# usb_hub.net
KiCad netlist of a schematic drawn in EAGLE
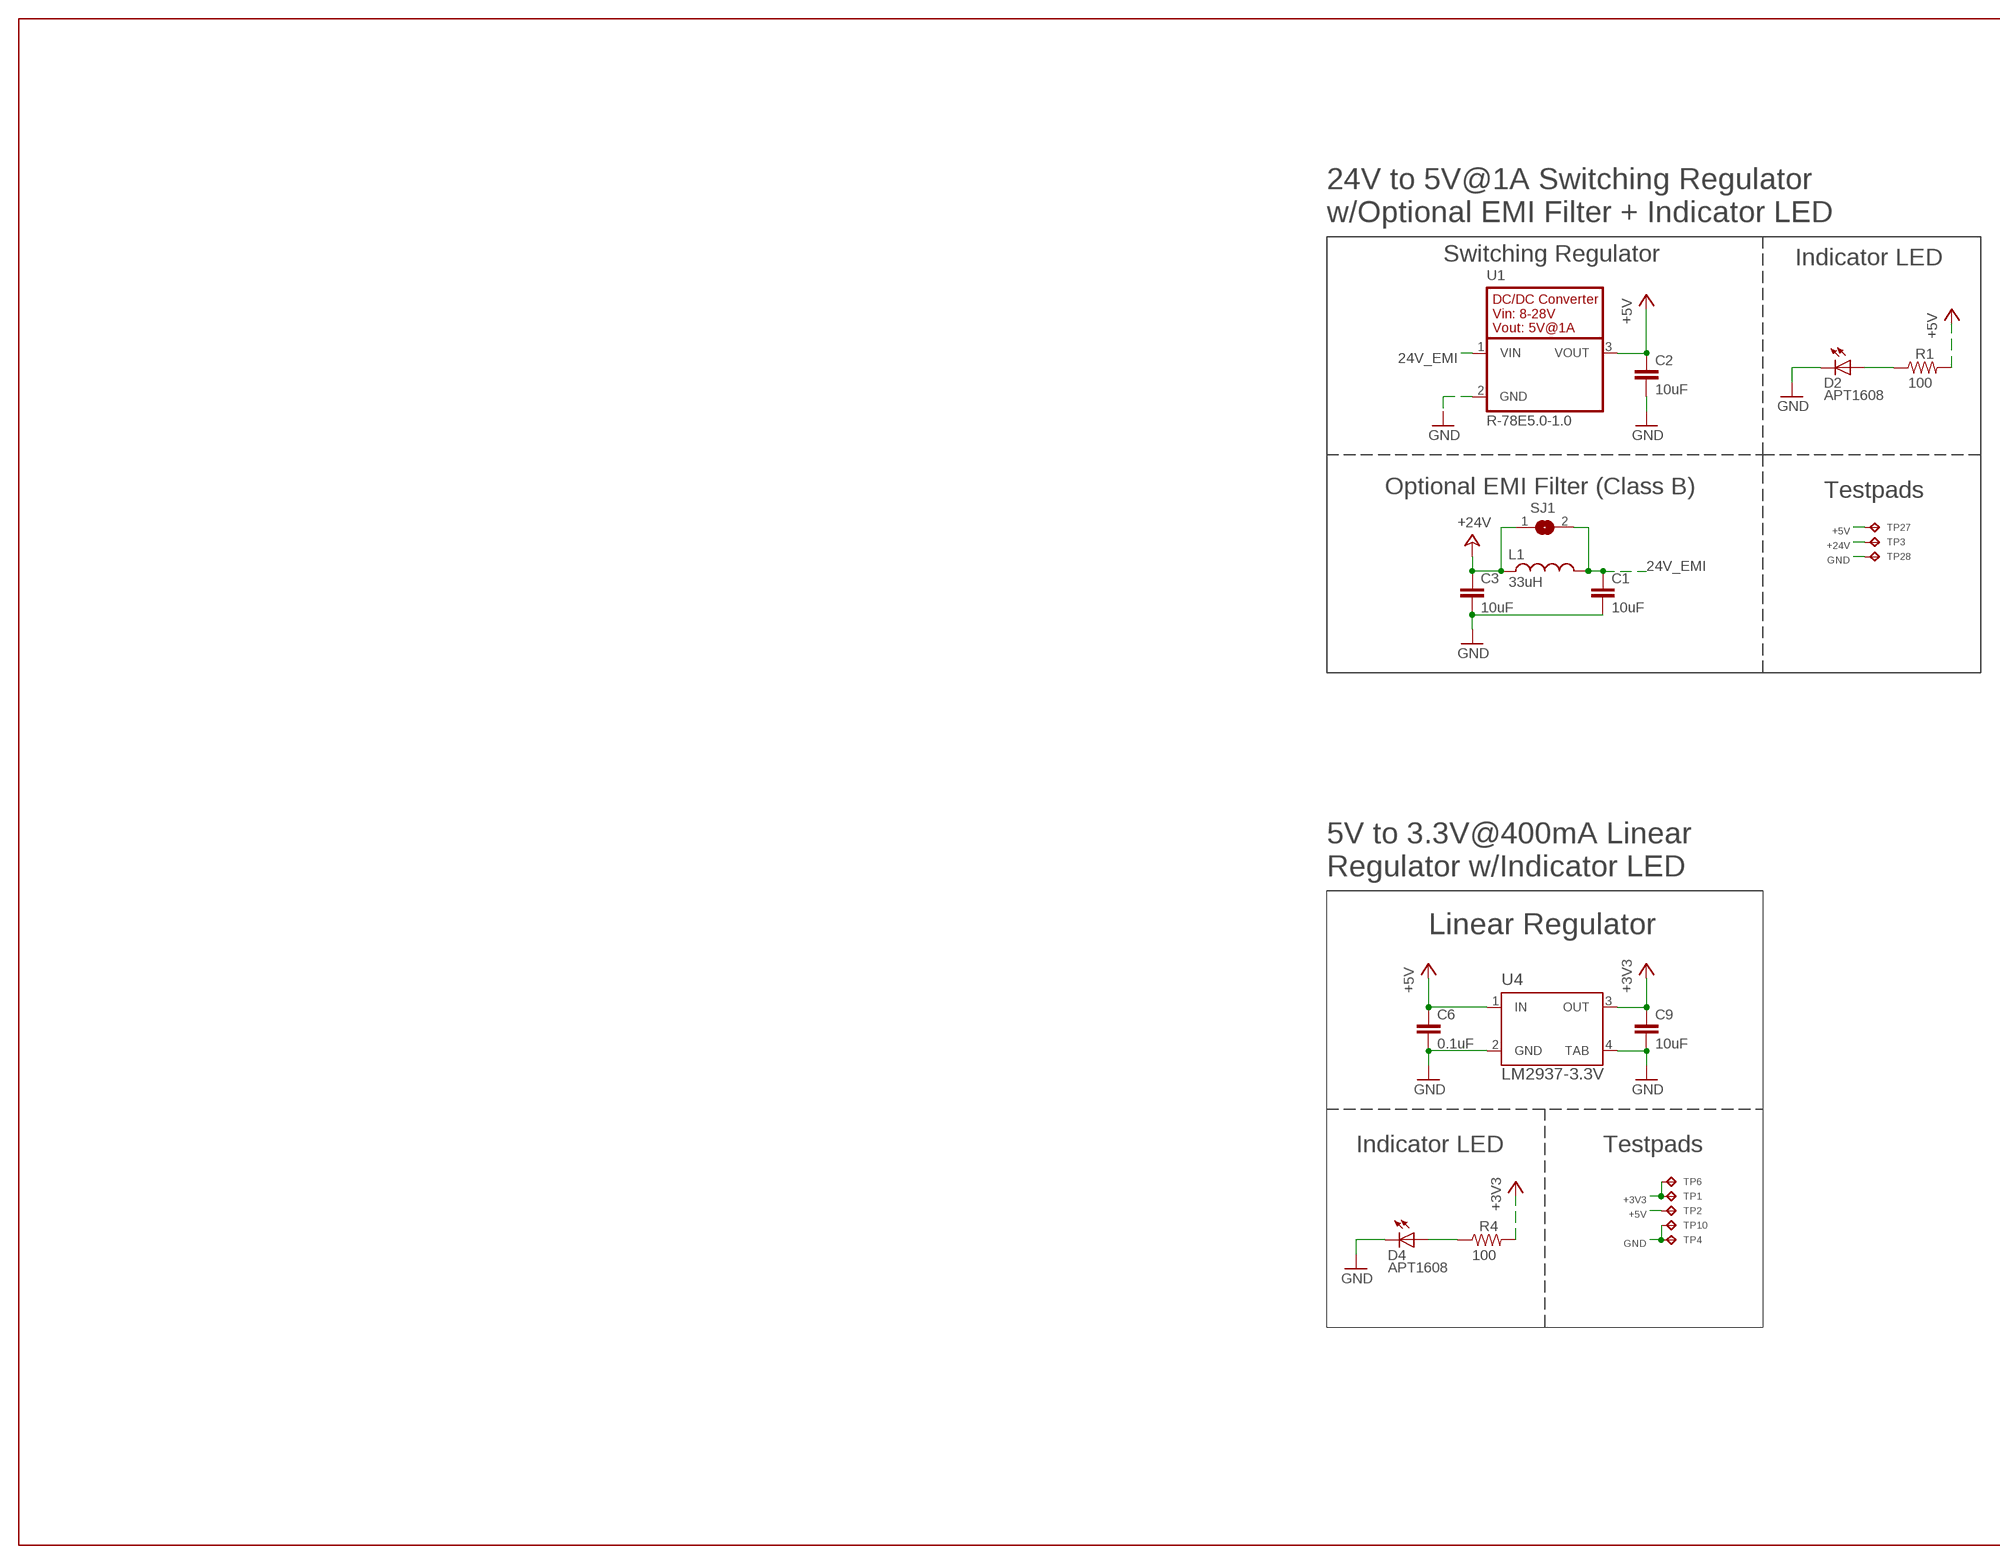
[diagram p0: schematic, sheet 1, part 1 of 2]
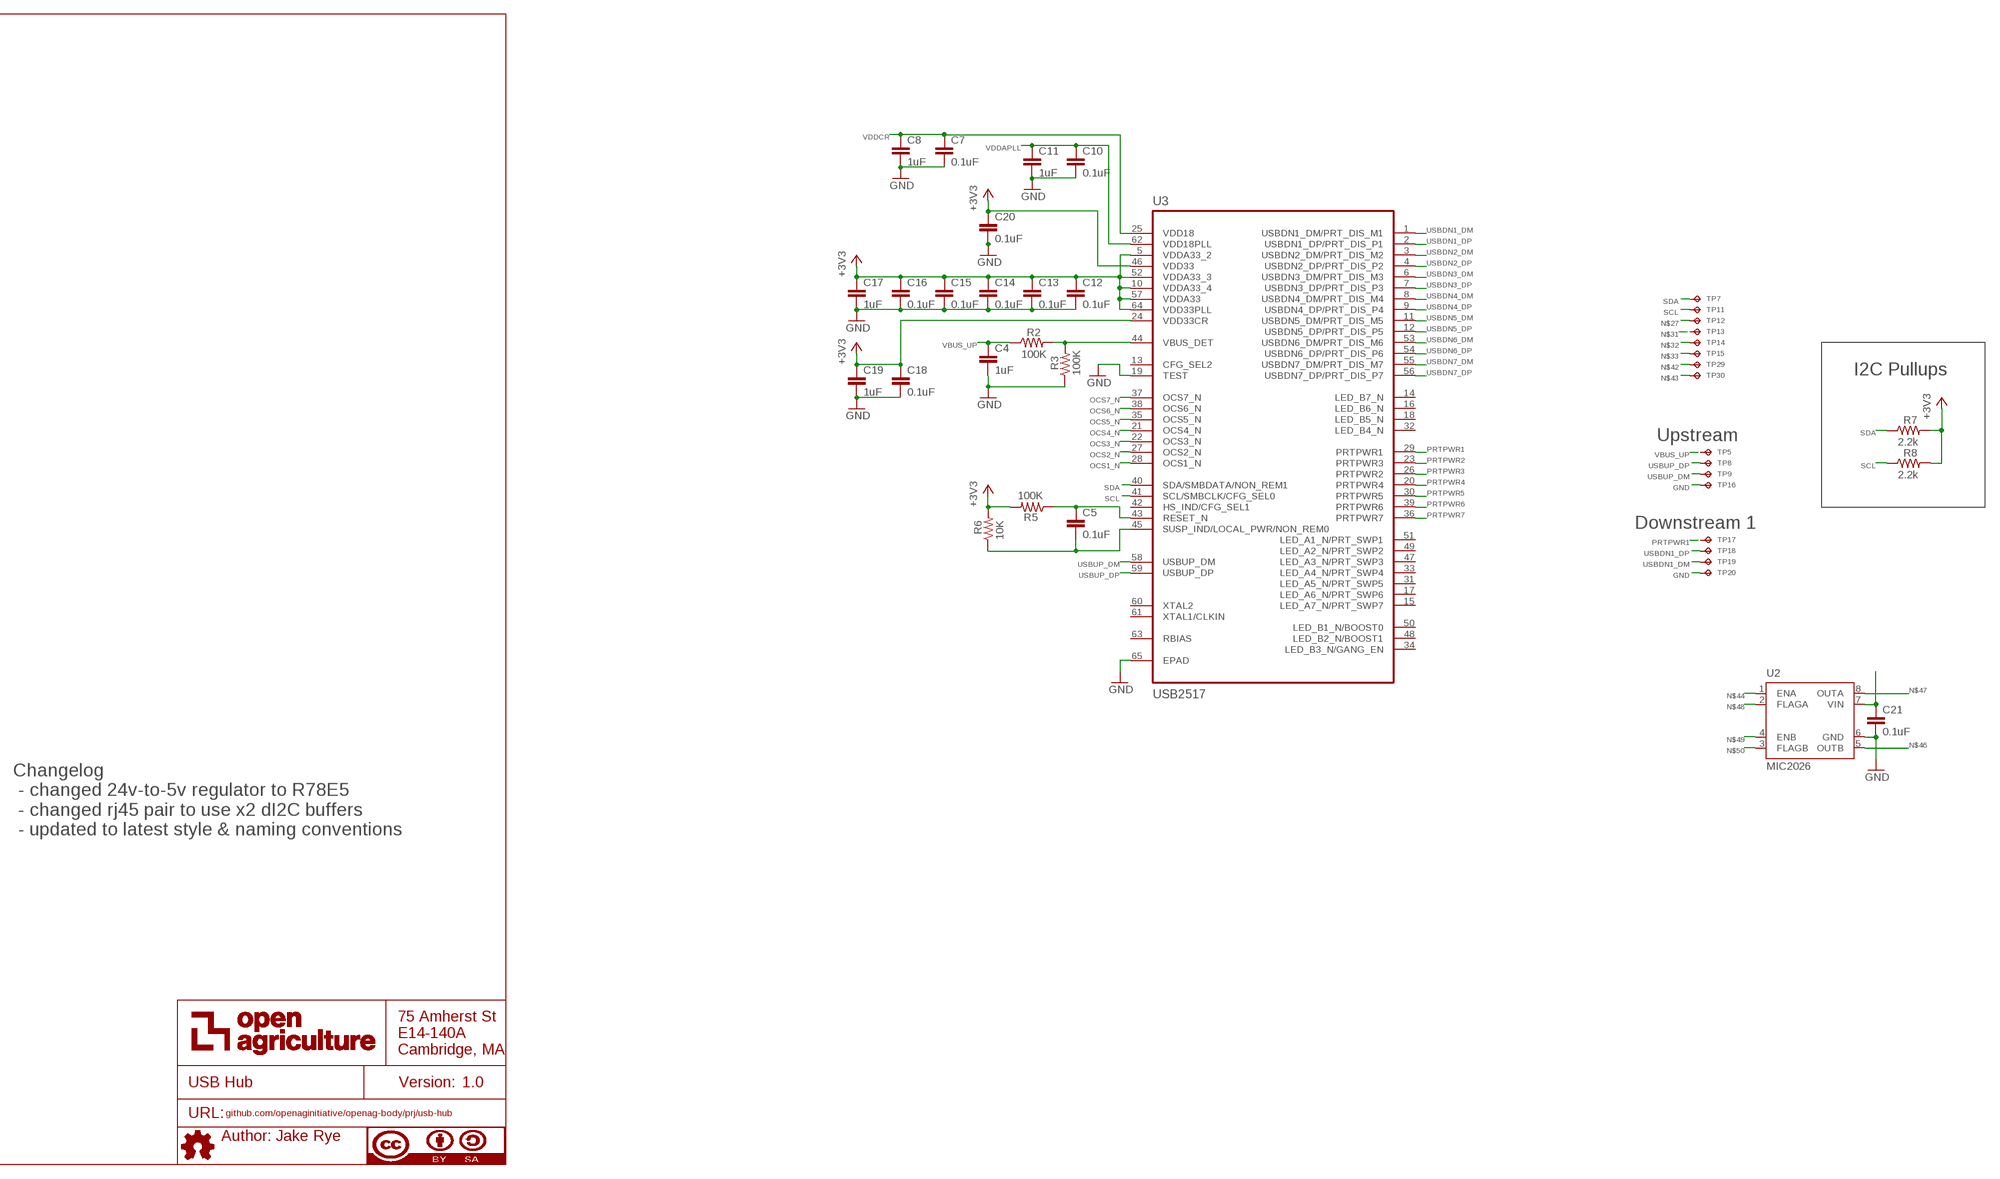
[diagram p1: schematic, sheet 1, part 2 of 2]

(export (version "E")
  (design (tool "Eeschema 10.0.6"))
  (components
    (comp (ref "C1")
      (value "10uF")
      (footprint "eagle-import:C0805")
      (fields (field (name "MANUFACTURER") "Taiyo Yuden") (field (name "MPN") "GMK212BBJ106KG-T"))
      (libsource (lib "eagle-import") (part "10UF-GMK212BBJ106KG-T"))
    )
    (comp (ref "C2")
      (value "10uF")
      (footprint "eagle-import:C0805")
      (fields (field (name "MANUFACTURER") "Taiyo Yuden") (field (name "MPN") "GMK212BBJ106KG-T"))
      (libsource (lib "eagle-import") (part "10UF-GMK212BBJ106KG-T"))
    )
    (comp (ref "C3")
      (value "10uF")
      (footprint "eagle-import:C0805")
      (fields (field (name "MANUFACTURER") "Taiyo Yuden") (field (name "MPN") "GMK212BBJ106KG-T"))
      (libsource (lib "eagle-import") (part "10UF-GMK212BBJ106KG-T"))
    )
    (comp (ref "C4")
      (value "1uF")
      (footprint "eagle-import:C0603")
      (fields
        (field (name "MANUFACTURER") "Samsung Electro-Mechanics")
        (field (name "MPN") "CL10A105KB8NNNC")
      )
      (libsource (lib "eagle-import") (part "1UF-CL10A105KB8NNNC"))
    )
    (comp (ref "C5")
      (value "0.1uF")
      (footprint "eagle-import:C0603")
      (fields (field (name "MANUFACTURER") "Kemet") (field (name "MPN") "C0603C104K5RACTU"))
      (libsource (lib "eagle-import") (part "0.1UF-C0603C104K5RACTU"))
    )
    (comp (ref "C6")
      (value "0.1uF")
      (footprint "eagle-import:C0603")
      (fields (field (name "MANUFACTURER") "Kemet") (field (name "MPN") "C0603C104K5RACTU"))
      (libsource (lib "eagle-import") (part "0.1UF-C0603C104K5RACTU"))
    )
    (comp (ref "C7")
      (value "0.1uF")
      (footprint "eagle-import:C0603")
      (fields (field (name "MANUFACTURER") "Kemet") (field (name "MPN") "C0603C104K5RACTU"))
      (libsource (lib "eagle-import") (part "0.1UF-C0603C104K5RACTU"))
    )
    (comp (ref "C8")
      (value "1uF")
      (footprint "eagle-import:C0603")
      (fields
        (field (name "MANUFACTURER") "Samsung Electro-Mechanics")
        (field (name "MPN") "CL10A105KB8NNNC")
      )
      (libsource (lib "eagle-import") (part "1UF-CL10A105KB8NNNC"))
    )
    (comp (ref "C9")
      (value "10uF")
      (footprint "eagle-import:C0805")
      (fields (field (name "MANUFACTURER") "Taiyo Yuden") (field (name "MPN") "GMK212BBJ106KG-T"))
      (libsource (lib "eagle-import") (part "10UF-GMK212BBJ106KG-T"))
    )
    (comp (ref "C10")
      (value "0.1uF")
      (footprint "eagle-import:C0603")
      (fields (field (name "MANUFACTURER") "Kemet") (field (name "MPN") "C0603C104K5RACTU"))
      (libsource (lib "eagle-import") (part "0.1UF-C0603C104K5RACTU"))
    )
    (comp (ref "C11")
      (value "1uF")
      (footprint "eagle-import:C0603")
      (fields
        (field (name "MANUFACTURER") "Samsung Electro-Mechanics")
        (field (name "MPN") "CL10A105KB8NNNC")
      )
      (libsource (lib "eagle-import") (part "1UF-CL10A105KB8NNNC"))
    )
    (comp (ref "C12")
      (value "0.1uF")
      (footprint "eagle-import:C0603")
      (fields (field (name "MANUFACTURER") "Kemet") (field (name "MPN") "C0603C104K5RACTU"))
      (libsource (lib "eagle-import") (part "0.1UF-C0603C104K5RACTU"))
    )
    (comp (ref "C13")
      (value "0.1uF")
      (footprint "eagle-import:C0603")
      (fields (field (name "MANUFACTURER") "Kemet") (field (name "MPN") "C0603C104K5RACTU"))
      (libsource (lib "eagle-import") (part "0.1UF-C0603C104K5RACTU"))
    )
    (comp (ref "C14")
      (value "0.1uF")
      (footprint "eagle-import:C0603")
      (fields (field (name "MANUFACTURER") "Kemet") (field (name "MPN") "C0603C104K5RACTU"))
      (libsource (lib "eagle-import") (part "0.1UF-C0603C104K5RACTU"))
    )
    (comp (ref "C15")
      (value "0.1uF")
      (footprint "eagle-import:C0603")
      (fields (field (name "MANUFACTURER") "Kemet") (field (name "MPN") "C0603C104K5RACTU"))
      (libsource (lib "eagle-import") (part "0.1UF-C0603C104K5RACTU"))
    )
    (comp (ref "C16")
      (value "0.1uF")
      (footprint "eagle-import:C0603")
      (fields (field (name "MANUFACTURER") "Kemet") (field (name "MPN") "C0603C104K5RACTU"))
      (libsource (lib "eagle-import") (part "0.1UF-C0603C104K5RACTU"))
    )
    (comp (ref "C17")
      (value "1uF")
      (footprint "eagle-import:C0603")
      (fields
        (field (name "MANUFACTURER") "Samsung Electro-Mechanics")
        (field (name "MPN") "CL10A105KB8NNNC")
      )
      (libsource (lib "eagle-import") (part "1UF-CL10A105KB8NNNC"))
    )
    (comp (ref "C18")
      (value "0.1uF")
      (footprint "eagle-import:C0603")
      (fields (field (name "MANUFACTURER") "Kemet") (field (name "MPN") "C0603C104K5RACTU"))
      (libsource (lib "eagle-import") (part "0.1UF-C0603C104K5RACTU"))
    )
    (comp (ref "C19")
      (value "1uF")
      (footprint "eagle-import:C0603")
      (fields
        (field (name "MANUFACTURER") "Samsung Electro-Mechanics")
        (field (name "MPN") "CL10A105KB8NNNC")
      )
      (libsource (lib "eagle-import") (part "1UF-CL10A105KB8NNNC"))
    )
    (comp (ref "C20")
      (value "0.1uF")
      (footprint "eagle-import:C0603")
      (fields (field (name "MANUFACTURER") "Kemet") (field (name "MPN") "C0603C104K5RACTU"))
      (libsource (lib "eagle-import") (part "0.1UF-C0603C104K5RACTU"))
    )
    (comp (ref "C21")
      (value "0.1uF")
      (footprint "eagle-import:C0603")
      (fields (field (name "MANUFACTURER") "Kemet") (field (name "MPN") "C0603C104K5RACTU"))
      (libsource (lib "eagle-import") (part "0.1UF-C0603C104K5RACTU"))
    )
    (comp (ref "D2")
      (value "APT1608")
      (footprint "eagle-import:CHIPLED_0603")
      (fields (field (name "MANUFACTURER") "Kingbright") (field (name "MPN") "APT1608CGCK"))
      (libsource (lib "eagle-import") (part "APT1608CGCK"))
    )
    (comp (ref "D4")
      (value "APT1608")
      (footprint "eagle-import:CHIPLED_0603")
      (fields (field (name "MANUFACTURER") "Kingbright") (field (name "MPN") "APT1608CGCK"))
      (libsource (lib "eagle-import") (part "APT1608CGCK"))
    )
    (comp (ref "L1")
      (value "33uH")
      (footprint "eagle-import:29333C")
      (fields (field (name "MANUFACTURER") "Murata Power Solutions Inc.") (field (name "MPN") "29333C"))
      (libsource (lib "eagle-import") (part "33UH-29333C"))
    )
    (comp (ref "R1")
      (value "100")
      (footprint "eagle-import:RC0603N")
      (fields (field (name "MANUFACTURER") "Yageo") (field (name "MPN") "RC0603JR-07100RL"))
      (libsource (lib "eagle-import") (part "100OHM-RC0603JR-07100RL"))
    )
    (comp (ref "R2")
      (value "100K")
      (footprint "eagle-import:RC0603N")
      (libsource (lib "eagle-import") (part "100K-RC0603FR-07100KL"))
    )
    (comp (ref "R3")
      (value "100K")
      (footprint "eagle-import:RC0603N")
      (libsource (lib "eagle-import") (part "100K-RC0603FR-07100KL"))
    )
    (comp (ref "R4")
      (value "100")
      (footprint "eagle-import:RC0603N")
      (fields (field (name "MANUFACTURER") "Yageo") (field (name "MPN") "RC0603JR-07100RL"))
      (libsource (lib "eagle-import") (part "100OHM-RC0603JR-07100RL"))
    )
    (comp (ref "R5")
      (value "100K")
      (footprint "eagle-import:RC0603N")
      (libsource (lib "eagle-import") (part "100K-RC0603FR-07100KL"))
    )
    (comp (ref "R6")
      (value "10K")
      (footprint "eagle-import:RC0603N")
      (fields (field (name "MANUFACTURER") "Panasonic") (field (name "MPN") "ERJ-3EKF1002V"))
      (libsource (lib "eagle-import") (part "10K-ERJ-3EKF1002V"))
    )
    (comp (ref "R7")
      (value "2.2k")
      (footprint "eagle-import:RC0603N")
      (fields (field (name "MANUFACTURER") "Yageo") (field (name "MPN") "RC0603JR-072K2L"))
      (libsource (lib "eagle-import") (part "2.2K-RC0603JR-072K2L"))
    )
    (comp (ref "R8")
      (value "2.2k")
      (footprint "eagle-import:RC0603N")
      (fields (field (name "MANUFACTURER") "Yageo") (field (name "MPN") "RC0603JR-072K2L"))
      (libsource (lib "eagle-import") (part "2.2K-RC0603JR-072K2L"))
    )
    (comp (ref "SJ1")
      (value "SOLDERJUMPERREFLOW_NOPASTE")
      (footprint "eagle-import:SJ1")
      (libsource (lib "eagle-import") (part "SOLDERJUMPERREFLOW_NOPASTE"))
    )
    (comp (ref "TP1")
      (value "TPTP04R")
      (footprint "eagle-import:TP04R")
      (libsource (lib "eagle-import") (part "TPTP04R"))
    )
    (comp (ref "TP2")
      (value "TPTP04R")
      (footprint "eagle-import:TP04R")
      (libsource (lib "eagle-import") (part "TPTP04R"))
    )
    (comp (ref "TP3")
      (value "TPTP06R")
      (footprint "eagle-import:TP06R")
      (libsource (lib "eagle-import") (part "TPTP06R"))
    )
    (comp (ref "TP4")
      (value "TPTP04R")
      (footprint "eagle-import:TP04R")
      (libsource (lib "eagle-import") (part "TPTP04R"))
    )
    (comp (ref "TP5")
      (value "TPTP04R")
      (footprint "eagle-import:TP04R")
      (libsource (lib "eagle-import") (part "TPTP04R"))
    )
    (comp (ref "TP6")
      (value "TPTP04R")
      (footprint "eagle-import:TP04R")
      (libsource (lib "eagle-import") (part "TPTP04R"))
    )
    (comp (ref "TP7")
      (value "TPTP04R")
      (footprint "eagle-import:TP04R")
      (libsource (lib "eagle-import") (part "TPTP04R"))
    )
    (comp (ref "TP8")
      (value "TPTP04R")
      (footprint "eagle-import:TP04R")
      (libsource (lib "eagle-import") (part "TPTP04R"))
    )
    (comp (ref "TP9")
      (value "TPTP04R")
      (footprint "eagle-import:TP04R")
      (libsource (lib "eagle-import") (part "TPTP04R"))
    )
    (comp (ref "TP10")
      (value "TPTP04R")
      (footprint "eagle-import:TP04R")
      (libsource (lib "eagle-import") (part "TPTP04R"))
    )
    (comp (ref "TP11")
      (value "TPTP04R")
      (footprint "eagle-import:TP04R")
      (libsource (lib "eagle-import") (part "TPTP04R"))
    )
    (comp (ref "TP12")
      (value "TPTP04R")
      (footprint "eagle-import:TP04R")
      (libsource (lib "eagle-import") (part "TPTP04R"))
    )
    (comp (ref "TP13")
      (value "TPTP04R")
      (footprint "eagle-import:TP04R")
      (libsource (lib "eagle-import") (part "TPTP04R"))
    )
    (comp (ref "TP14")
      (value "TPTP04R")
      (footprint "eagle-import:TP04R")
      (libsource (lib "eagle-import") (part "TPTP04R"))
    )
    (comp (ref "TP15")
      (value "TPTP04R")
      (footprint "eagle-import:TP04R")
      (libsource (lib "eagle-import") (part "TPTP04R"))
    )
    (comp (ref "TP16")
      (value "TPTP04R")
      (footprint "eagle-import:TP04R")
      (libsource (lib "eagle-import") (part "TPTP04R"))
    )
    (comp (ref "TP17")
      (value "TPTP04R")
      (footprint "eagle-import:TP04R")
      (libsource (lib "eagle-import") (part "TPTP04R"))
    )
    (comp (ref "TP18")
      (value "TPTP04R")
      (footprint "eagle-import:TP04R")
      (libsource (lib "eagle-import") (part "TPTP04R"))
    )
    (comp (ref "TP19")
      (value "TPTP04R")
      (footprint "eagle-import:TP04R")
      (libsource (lib "eagle-import") (part "TPTP04R"))
    )
    (comp (ref "TP20")
      (value "TPTP04R")
      (footprint "eagle-import:TP04R")
      (libsource (lib "eagle-import") (part "TPTP04R"))
    )
    (comp (ref "TP27")
      (value "TPTP06R")
      (footprint "eagle-import:TP06R")
      (libsource (lib "eagle-import") (part "TPTP06R"))
    )
    (comp (ref "TP28")
      (value "TPTP06R")
      (footprint "eagle-import:TP06R")
      (libsource (lib "eagle-import") (part "TPTP06R"))
    )
    (comp (ref "TP29")
      (value "TPTP04R")
      (footprint "eagle-import:TP04R")
      (libsource (lib "eagle-import") (part "TPTP04R"))
    )
    (comp (ref "TP30")
      (value "TPTP04R")
      (footprint "eagle-import:TP04R")
      (libsource (lib "eagle-import") (part "TPTP04R"))
    )
    (comp (ref "U$6")
      (value "AUTHOR")
      (footprint "eagle-import:AUTHOR")
      (fields (field (name "AUTHOR") "Jake Rye"))
      (libsource (lib "eagle-import") (part "AUTHOR"))
    )
    (comp (ref "U$7")
      (value "TITLE")
      (footprint "eagle-import:TITLE")
      (fields
        (field (name "TITLE") "USB Hub")
        (field (name "URL") "github.com/openaginitiative/openag-body/prj/usb-hub")
      )
      (libsource (lib "eagle-import") (part "TITLE"))
    )
    (comp (ref "U1")
      (value "R-78E5.0-1.0")
      (footprint "eagle-import:R-78E5.0-1.0")
      (fields (field (name "MANUFACTURER") "Recom Power"))
      (libsource (lib "eagle-import") (part "R-78E5.0-1.0"))
    )
    (comp (ref "U2")
      (value "MIC2026")
      (footprint "eagle-import:SOIC8")
      (fields (field (name "MANUFACTURER") "Microchip Technology") (field (name "MPN") "MIC2026-1YM-TR"))
      (libsource (lib "eagle-import") (part "MIC2026-1YM-TR"))
    )
    (comp (ref "U3")
      (value "USB2517")
      (footprint "eagle-import:QFN50P900X900X100-65N")
      (fields (field (name "MANUFACTURER") "Microchip Technology") (field (name "MPN") "USB2517-JZX"))
      (libsource (lib "eagle-import") (part "USB2517-JZX"))
    )
    (comp (ref "U4")
      (value "LM2937-3.3V")
      (footprint "eagle-import:MP04A")
      (fields (field (name "MANUFACTURER") "Texas Instruments") (field (name "MPN") "LM2937IMP-3.3/NOPB"))
      (libsource (lib "eagle-import") (part "LM2937IMP-3.3/NOPB"))
    )
  )
  (nets
    (net (code "1") (name "+3V3") (class "Default")
      (node (ref "C12") (pin "1") (pinfunction "1_1") (pintype "passive"))
      (node (ref "C13") (pin "1") (pinfunction "1_1") (pintype "passive"))
      (node (ref "C14") (pin "1") (pinfunction "1_1") (pintype "passive"))
      (node (ref "C15") (pin "1") (pinfunction "1_1") (pintype "passive"))
      (node (ref "C16") (pin "1") (pinfunction "1_1") (pintype "passive"))
      (node (ref "C17") (pin "1") (pinfunction "1_1") (pintype "passive"))
      (node (ref "C18") (pin "1") (pinfunction "1_1") (pintype "passive"))
      (node (ref "C19") (pin "1") (pinfunction "1_1") (pintype "passive"))
      (node (ref "C20") (pin "1") (pinfunction "1_1") (pintype "passive"))
      (node (ref "C9") (pin "1") (pinfunction "1_1") (pintype "passive"))
      (node (ref "R4") (pin "2") (pinfunction "2_2") (pintype "passive"))
      (node (ref "R5") (pin "2") (pinfunction "2_2") (pintype "passive"))
      (node (ref "R6") (pin "2") (pinfunction "2_2") (pintype "passive"))
      (node (ref "R7") (pin "2") (pinfunction "2_2") (pintype "passive"))
      (node (ref "R8") (pin "2") (pinfunction "2_2") (pintype "passive"))
      (node (ref "TP1") (pin "1") (pinfunction "TP_1") (pintype "input"))
      (node (ref "TP6") (pin "1") (pinfunction "TP_1") (pintype "input"))
      (node (ref "U3") (pin "10") (pinfunction "VDDA33_4_10") (pintype "power_in"))
      (node (ref "U3") (pin "24") (pinfunction "VDD33CR_24") (pintype "power_in"))
      (node (ref "U3") (pin "46") (pinfunction "VDD33_46") (pintype "power_in"))
      (node (ref "U3") (pin "5") (pinfunction "VDDA33_2_5") (pintype "power_in"))
      (node (ref "U3") (pin "52") (pinfunction "VDDA33_3_52") (pintype "power_in"))
      (node (ref "U3") (pin "57") (pinfunction "VDDA33_57") (pintype "power_in"))
      (node (ref "U3") (pin "64") (pinfunction "VDD33PLL_64") (pintype "power_in"))
      (node (ref "U4") (pin "3") (pinfunction "OUT_3") (pintype "power_in"))
    )
    (net (code "2") (name "+5V") (class "Default")
      (node (ref "C2") (pin "1") (pinfunction "1_1") (pintype "passive"))
      (node (ref "C6") (pin "1") (pinfunction "1_1") (pintype "passive"))
      (node (ref "R1") (pin "2") (pinfunction "2_2") (pintype "passive"))
      (node (ref "TP2") (pin "1") (pinfunction "TP_1") (pintype "input"))
      (node (ref "TP27") (pin "TP") (pinfunction "TP_TP") (pintype "input"))
      (node (ref "U1") (pin "3") (pinfunction "VOUT_3") (pintype "passive"))
      (node (ref "U4") (pin "1") (pinfunction "IN_1") (pintype "power_in"))
    )
    (net (code "3") (name "+24V") (class "Default")
      (node (ref "C3") (pin "1") (pinfunction "1_1") (pintype "passive"))
      (node (ref "L1") (pin "1") (pinfunction "1_1") (pintype "passive"))
      (node (ref "SJ1") (pin "1") (pinfunction "1_1") (pintype "passive"))
      (node (ref "TP3") (pin "TP") (pinfunction "TP_TP") (pintype "input"))
    )
    (net (code "4") (name "24V_EMI") (class "Default")
      (node (ref "C1") (pin "1") (pinfunction "1_1") (pintype "passive"))
      (node (ref "L1") (pin "2") (pinfunction "2_2") (pintype "passive"))
      (node (ref "SJ1") (pin "2") (pinfunction "2_2") (pintype "passive"))
      (node (ref "U1") (pin "1") (pinfunction "VIN_1") (pintype "passive"))
    )
    (net (code "5") (name "GND") (class "Default")
      (node (ref "C1") (pin "2") (pinfunction "2_2") (pintype "passive"))
      (node (ref "C10") (pin "2") (pinfunction "2_2") (pintype "passive"))
      (node (ref "C11") (pin "2") (pinfunction "2_2") (pintype "passive"))
      (node (ref "C12") (pin "2") (pinfunction "2_2") (pintype "passive"))
      (node (ref "C13") (pin "2") (pinfunction "2_2") (pintype "passive"))
      (node (ref "C14") (pin "2") (pinfunction "2_2") (pintype "passive"))
      (node (ref "C15") (pin "2") (pinfunction "2_2") (pintype "passive"))
      (node (ref "C16") (pin "2") (pinfunction "2_2") (pintype "passive"))
      (node (ref "C17") (pin "2") (pinfunction "2_2") (pintype "passive"))
      (node (ref "C18") (pin "2") (pinfunction "2_2") (pintype "passive"))
      (node (ref "C19") (pin "2") (pinfunction "2_2") (pintype "passive"))
      (node (ref "C2") (pin "2") (pinfunction "2_2") (pintype "passive"))
      (node (ref "C20") (pin "2") (pinfunction "2_2") (pintype "passive"))
      (node (ref "C21") (pin "2") (pinfunction "2_2") (pintype "passive"))
      (node (ref "C3") (pin "2") (pinfunction "2_2") (pintype "passive"))
      (node (ref "C4") (pin "2") (pinfunction "2_2") (pintype "passive"))
      (node (ref "C6") (pin "2") (pinfunction "2_2") (pintype "passive"))
      (node (ref "C7") (pin "2") (pinfunction "2_2") (pintype "passive"))
      (node (ref "C8") (pin "2") (pinfunction "2_2") (pintype "passive"))
      (node (ref "C9") (pin "2") (pinfunction "2_2") (pintype "passive"))
      (node (ref "D2") (pin "C") (pinfunction "C_C") (pintype "passive"))
      (node (ref "D4") (pin "C") (pinfunction "C_C") (pintype "passive"))
      (node (ref "R3") (pin "1") (pinfunction "1_1") (pintype "passive"))
      (node (ref "TP10") (pin "1") (pinfunction "TP_1") (pintype "input"))
      (node (ref "TP16") (pin "1") (pinfunction "TP_1") (pintype "input"))
      (node (ref "TP20") (pin "1") (pinfunction "TP_1") (pintype "input"))
      (node (ref "TP28") (pin "TP") (pinfunction "TP_TP") (pintype "input"))
      (node (ref "TP4") (pin "1") (pinfunction "TP_1") (pintype "input"))
      (node (ref "U1") (pin "2") (pinfunction "GND_2") (pintype "passive"))
      (node (ref "U2") (pin "6") (pinfunction "GND_6") (pintype "bidirectional"))
      (node (ref "U3") (pin "19") (pinfunction "TEST_19") (pintype "input"))
      (node (ref "U3") (pin "65") (pinfunction "EPAD_65") (pintype "passive"))
      (node (ref "U4") (pin "2") (pinfunction "GND_2") (pintype "power_in"))
      (node (ref "U4") (pin "4") (pinfunction "TAB_4") (pintype "power_in"))
    )
    (net (code "6") (name "N$27") (class "Default")
      (node (ref "TP12") (pin "1") (pinfunction "TP_1") (pintype "input"))
    )
    (net (code "7") (name "N$31") (class "Default")
      (node (ref "TP13") (pin "1") (pinfunction "TP_1") (pintype "input"))
    )
    (net (code "8") (name "N$32") (class "Default")
      (node (ref "TP14") (pin "1") (pinfunction "TP_1") (pintype "input"))
    )
    (net (code "9") (name "N$33") (class "Default")
      (node (ref "TP15") (pin "1") (pinfunction "TP_1") (pintype "input"))
    )
    (net (code "10") (name "N$42") (class "Default")
      (node (ref "TP29") (pin "1") (pinfunction "TP_1") (pintype "input"))
    )
    (net (code "11") (name "N$43") (class "Default")
      (node (ref "TP30") (pin "1") (pinfunction "TP_1") (pintype "input"))
    )
    (net (code "12") (name "N$44") (class "Default")
      (node (ref "U2") (pin "1") (pinfunction "ENA_1") (pintype "bidirectional"))
    )
    (net (code "13") (name "N$46") (class "Default")
      (node (ref "U2") (pin "5") (pinfunction "OUTB_5") (pintype "bidirectional"))
    )
    (net (code "14") (name "N$47") (class "Default")
      (node (ref "U2") (pin "8") (pinfunction "OUTA_8") (pintype "bidirectional"))
    )
    (net (code "15") (name "N$48") (class "Default")
      (node (ref "U2") (pin "2") (pinfunction "FLAGA_2") (pintype "bidirectional"))
    )
    (net (code "16") (name "N$49") (class "Default")
      (node (ref "U2") (pin "4") (pinfunction "ENB_4") (pintype "bidirectional"))
    )
    (net (code "17") (name "N$50") (class "Default")
      (node (ref "U2") (pin "3") (pinfunction "FLAGB_3") (pintype "bidirectional"))
    )
    (net (code "18") (name "Net-(D2-PadA)") (class "Default")
      (node (ref "D2") (pin "A") (pinfunction "A_A") (pintype "passive"))
      (node (ref "R1") (pin "1") (pinfunction "1_1") (pintype "passive"))
    )
    (net (code "19") (name "Net-(D4-PadA)") (class "Default")
      (node (ref "D4") (pin "A") (pinfunction "A_A") (pintype "passive"))
      (node (ref "R4") (pin "1") (pinfunction "1_1") (pintype "passive"))
    )
    (net (code "20") (name "Net-(U2-VIN)") (class "Default")
      (node (ref "C21") (pin "1") (pinfunction "1_1") (pintype "passive"))
      (node (ref "U2") (pin "7") (pinfunction "VIN_7") (pintype "bidirectional"))
    )
    (net (code "21") (name "Net-(U3-RESET_N)") (class "Default")
      (node (ref "C5") (pin "1") (pinfunction "1_1") (pintype "passive"))
      (node (ref "R5") (pin "1") (pinfunction "1_1") (pintype "passive"))
      (node (ref "U3") (pin "43") (pinfunction "RESET_N_43") (pintype "input"))
    )
    (net (code "22") (name "Net-(U3-SUSP_IND{slash}LOCAL_PWR{slash}NON_REM0)") (class "Default")
      (node (ref "C5") (pin "2") (pinfunction "2_2") (pintype "passive"))
      (node (ref "R6") (pin "1") (pinfunction "1_1") (pintype "passive"))
      (node (ref "U3") (pin "45") (pinfunction "SUSP_IND/LOCAL_PWR/NON_REM0_45") (pintype "bidirectional"))
    )
    (net (code "23") (name "Net-(U3-VBUS_DET)") (class "Default")
      (node (ref "R2") (pin "2") (pinfunction "2_2") (pintype "passive"))
      (node (ref "R3") (pin "2") (pinfunction "2_2") (pintype "passive"))
      (node (ref "U3") (pin "44") (pinfunction "VBUS_DET_44") (pintype "power_in"))
    )
    (net (code "24") (name "OCS1_N") (class "Default")
      (node (ref "U3") (pin "28") (pinfunction "OCS1_N_28") (pintype "input"))
    )
    (net (code "25") (name "OCS2_N") (class "Default")
      (node (ref "U3") (pin "27") (pinfunction "OCS2_N_27") (pintype "input"))
    )
    (net (code "26") (name "OCS3_N") (class "Default")
      (node (ref "U3") (pin "22") (pinfunction "OCS3_N_22") (pintype "input"))
    )
    (net (code "27") (name "OCS4_N") (class "Default")
      (node (ref "U3") (pin "21") (pinfunction "OCS4_N_21") (pintype "input"))
    )
    (net (code "28") (name "OCS5_N") (class "Default")
      (node (ref "U3") (pin "35") (pinfunction "OCS5_N_35") (pintype "input"))
    )
    (net (code "29") (name "OCS6_N") (class "Default")
      (node (ref "U3") (pin "38") (pinfunction "OCS6_N_38") (pintype "input"))
    )
    (net (code "30") (name "OCS7_N") (class "Default")
      (node (ref "U3") (pin "37") (pinfunction "OCS7_N_37") (pintype "input"))
    )
    (net (code "31") (name "PRTPWR1") (class "Default")
      (node (ref "TP17") (pin "1") (pinfunction "TP_1") (pintype "input"))
      (node (ref "U3") (pin "29") (pinfunction "PRTPWR1_29") (pintype "output"))
    )
    (net (code "32") (name "PRTPWR2") (class "Default")
      (node (ref "U3") (pin "23") (pinfunction "PRTPWR3_23") (pintype "output"))
    )
    (net (code "33") (name "PRTPWR3") (class "Default")
      (node (ref "U3") (pin "26") (pinfunction "PRTPWR2_26") (pintype "output"))
    )
    (net (code "34") (name "PRTPWR4") (class "Default")
      (node (ref "U3") (pin "20") (pinfunction "PRTPWR4_20") (pintype "output"))
    )
    (net (code "35") (name "PRTPWR5") (class "Default")
      (node (ref "U3") (pin "30") (pinfunction "PRTPWR5_30") (pintype "output"))
    )
    (net (code "36") (name "PRTPWR6") (class "Default")
      (node (ref "U3") (pin "39") (pinfunction "PRTPWR6_39") (pintype "output"))
    )
    (net (code "37") (name "PRTPWR7") (class "Default")
      (node (ref "U3") (pin "36") (pinfunction "PRTPWR7_36") (pintype "output"))
    )
    (net (code "38") (name "SCL") (class "Default")
      (node (ref "R8") (pin "1") (pinfunction "1_1") (pintype "passive"))
      (node (ref "TP11") (pin "1") (pinfunction "TP_1") (pintype "input"))
      (node (ref "U3") (pin "41") (pinfunction "SCL/SMBCLK/CFG_SEL0_41") (pintype "bidirectional"))
    )
    (net (code "39") (name "SDA") (class "Default")
      (node (ref "R7") (pin "1") (pinfunction "1_1") (pintype "passive"))
      (node (ref "TP7") (pin "1") (pinfunction "TP_1") (pintype "input"))
      (node (ref "U3") (pin "40") (pinfunction "SDA/SMBDATA/NON_REM1_40") (pintype "bidirectional"))
    )
    (net (code "40") (name "USBDN1_DM") (class "Default")
      (node (ref "TP19") (pin "1") (pinfunction "TP_1") (pintype "input"))
      (node (ref "U3") (pin "1") (pinfunction "USBDN1_DM/PRT_DIS_M1_1") (pintype "bidirectional"))
    )
    (net (code "41") (name "USBDN1_DP") (class "Default")
      (node (ref "TP18") (pin "1") (pinfunction "TP_1") (pintype "input"))
      (node (ref "U3") (pin "2") (pinfunction "USBDN1_DP/PRT_DIS_P1_2") (pintype "bidirectional"))
    )
    (net (code "42") (name "USBDN2_DM") (class "Default")
      (node (ref "U3") (pin "3") (pinfunction "USBDN2_DM/PRT_DIS_M2_3") (pintype "bidirectional"))
    )
    (net (code "43") (name "USBDN2_DP") (class "Default")
      (node (ref "U3") (pin "4") (pinfunction "USBDN2_DP/PRT_DIS_P2_4") (pintype "bidirectional"))
    )
    (net (code "44") (name "USBDN3_DM") (class "Default")
      (node (ref "U3") (pin "6") (pinfunction "USBDN3_DM/PRT_DIS_M3_6") (pintype "bidirectional"))
    )
    (net (code "45") (name "USBDN3_DP") (class "Default")
      (node (ref "U3") (pin "7") (pinfunction "USBDN3_DP/PRT_DIS_P3_7") (pintype "bidirectional"))
    )
    (net (code "46") (name "USBDN4_DM") (class "Default")
      (node (ref "U3") (pin "8") (pinfunction "USBDN4_DM/PRT_DIS_M4_8") (pintype "bidirectional"))
    )
    (net (code "47") (name "USBDN4_DP") (class "Default")
      (node (ref "U3") (pin "9") (pinfunction "USBDN4_DP/PRT_DIS_P4_9") (pintype "bidirectional"))
    )
    (net (code "48") (name "USBDN5_DM") (class "Default")
      (node (ref "U3") (pin "11") (pinfunction "USBDN5_DM/PRT_DIS_M5_11") (pintype "bidirectional"))
    )
    (net (code "49") (name "USBDN5_DP") (class "Default")
      (node (ref "U3") (pin "12") (pinfunction "USBDN5_DP/PRT_DIS_P5_12") (pintype "bidirectional"))
    )
    (net (code "50") (name "USBDN6_DM") (class "Default")
      (node (ref "U3") (pin "53") (pinfunction "USBDN6_DM/PRT_DIS_M6_53") (pintype "bidirectional"))
    )
    (net (code "51") (name "USBDN6_DP") (class "Default")
      (node (ref "U3") (pin "54") (pinfunction "USBDN6_DP/PRT_DIS_P6_54") (pintype "bidirectional"))
    )
    (net (code "52") (name "USBDN7_DM") (class "Default")
      (node (ref "U3") (pin "55") (pinfunction "USBDN7_DM/PRT_DIS_M7_55") (pintype "bidirectional"))
    )
    (net (code "53") (name "USBDN7_DP") (class "Default")
      (node (ref "U3") (pin "56") (pinfunction "USBDN7_DP/PRT_DIS_P7_56") (pintype "bidirectional"))
    )
    (net (code "54") (name "USBUP_DM") (class "Default")
      (node (ref "TP9") (pin "1") (pinfunction "TP_1") (pintype "input"))
      (node (ref "U3") (pin "58") (pinfunction "USBUP_DM_58") (pintype "bidirectional"))
    )
    (net (code "55") (name "USBUP_DP") (class "Default")
      (node (ref "TP8") (pin "1") (pinfunction "TP_1") (pintype "input"))
      (node (ref "U3") (pin "59") (pinfunction "USBUP_DP_59") (pintype "bidirectional"))
    )
    (net (code "56") (name "VBUS_UP") (class "Default")
      (node (ref "C4") (pin "1") (pinfunction "1_1") (pintype "passive"))
      (node (ref "R2") (pin "1") (pinfunction "1_1") (pintype "passive"))
      (node (ref "TP5") (pin "1") (pinfunction "TP_1") (pintype "input"))
    )
    (net (code "57") (name "VDDAPLL") (class "Default")
      (node (ref "C10") (pin "1") (pinfunction "1_1") (pintype "passive"))
      (node (ref "C11") (pin "1") (pinfunction "1_1") (pintype "passive"))
      (node (ref "U3") (pin "62") (pinfunction "VDD18PLL_62") (pintype "power_in"))
    )
    (net (code "58") (name "VDDCR") (class "Default")
      (node (ref "C7") (pin "1") (pinfunction "1_1") (pintype "passive"))
      (node (ref "C8") (pin "1") (pinfunction "1_1") (pintype "passive"))
      (node (ref "U3") (pin "25") (pinfunction "VDD18_25") (pintype "power_in"))
    )
    (net (code "59") (name "unconnected-(U3-CFG_SEL2-Pad13)") (class "Default")
      (node (ref "U3") (pin "13") (pinfunction "CFG_SEL2_13") (pintype "input"))
    )
    (net (code "60") (name "unconnected-(U3-HS_IND{slash}CFG_SEL1-Pad42)") (class "Default")
      (node (ref "U3") (pin "42") (pinfunction "HS_IND/CFG_SEL1_42") (pintype "bidirectional"))
    )
    (net (code "61") (name "unconnected-(U3-LED_A1_N{slash}PRT_SWP1-Pad51)") (class "Default")
      (node (ref "U3") (pin "51") (pinfunction "LED_A1_N/PRT_SWP1_51") (pintype "bidirectional"))
    )
    (net (code "62") (name "unconnected-(U3-LED_A2_N{slash}PRT_SWP2-Pad49)") (class "Default")
      (node (ref "U3") (pin "49") (pinfunction "LED_A2_N/PRT_SWP2_49") (pintype "bidirectional"))
    )
    (net (code "63") (name "unconnected-(U3-LED_A3_N{slash}PRT_SWP3-Pad47)") (class "Default")
      (node (ref "U3") (pin "47") (pinfunction "LED_A3_N/PRT_SWP3_47") (pintype "bidirectional"))
    )
    (net (code "64") (name "unconnected-(U3-LED_A4_N{slash}PRT_SWP4-Pad33)") (class "Default")
      (node (ref "U3") (pin "33") (pinfunction "LED_A4_N/PRT_SWP4_33") (pintype "bidirectional"))
    )
    (net (code "65") (name "unconnected-(U3-LED_A5_N{slash}PRT_SWP5-Pad31)") (class "Default")
      (node (ref "U3") (pin "31") (pinfunction "LED_A5_N/PRT_SWP5_31") (pintype "bidirectional"))
    )
    (net (code "66") (name "unconnected-(U3-LED_A6_N{slash}PRT_SWP6-Pad17)") (class "Default")
      (node (ref "U3") (pin "17") (pinfunction "LED_A6_N/PRT_SWP6_17") (pintype "bidirectional"))
    )
    (net (code "67") (name "unconnected-(U3-LED_A7_N{slash}PRT_SWP7-Pad15)") (class "Default")
      (node (ref "U3") (pin "15") (pinfunction "LED_A7_N/PRT_SWP7_15") (pintype "bidirectional"))
    )
    (net (code "68") (name "unconnected-(U3-LED_B1_N{slash}BOOST0-Pad50)") (class "Default")
      (node (ref "U3") (pin "50") (pinfunction "LED_B1_N/BOOST0_50") (pintype "bidirectional"))
    )
    (net (code "69") (name "unconnected-(U3-LED_B2_N{slash}BOOST1-Pad48)") (class "Default")
      (node (ref "U3") (pin "48") (pinfunction "LED_B2_N/BOOST1_48") (pintype "bidirectional"))
    )
    (net (code "70") (name "unconnected-(U3-LED_B3_N{slash}GANG_EN-Pad34)") (class "Default")
      (node (ref "U3") (pin "34") (pinfunction "LED_B3_N/GANG_EN_34") (pintype "bidirectional"))
    )
    (net (code "71") (name "unconnected-(U3-LED_B4_N-Pad32)") (class "Default")
      (node (ref "U3") (pin "32") (pinfunction "LED_B4_N_32") (pintype "bidirectional"))
    )
    (net (code "72") (name "unconnected-(U3-LED_B5_N-Pad18)") (class "Default")
      (node (ref "U3") (pin "18") (pinfunction "LED_B5_N_18") (pintype "bidirectional"))
    )
    (net (code "73") (name "unconnected-(U3-LED_B6_N-Pad16)") (class "Default")
      (node (ref "U3") (pin "16") (pinfunction "LED_B6_N_16") (pintype "bidirectional"))
    )
    (net (code "74") (name "unconnected-(U3-LED_B7_N-Pad14)") (class "Default")
      (node (ref "U3") (pin "14") (pinfunction "LED_B7_N_14") (pintype "bidirectional"))
    )
    (net (code "75") (name "unconnected-(U3-RBIAS-Pad63)") (class "Default")
      (node (ref "U3") (pin "63") (pinfunction "RBIAS_63") (pintype "input"))
    )
    (net (code "76") (name "unconnected-(U3-XTAL1{slash}CLKIN-Pad61)") (class "Default")
      (node (ref "U3") (pin "61") (pinfunction "XTAL1/CLKIN_61") (pintype "input"))
    )
    (net (code "77") (name "unconnected-(U3-XTAL2-Pad60)") (class "Default")
      (node (ref "U3") (pin "60") (pinfunction "XTAL2_60") (pintype "output"))
    )
  )
)
